# subckt_adc_TLC2574.net
KiCad netlist of a schematic drawn in Altium Designer
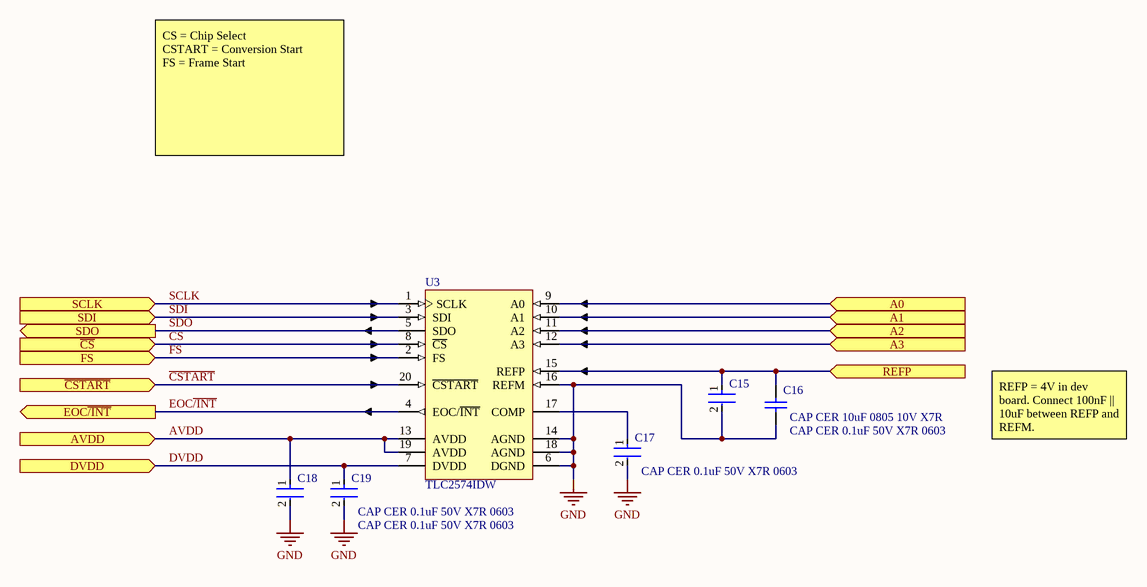
[diagram p0: subckt_adc_TLC2574.SchDoc]

(export (version "E")
  (design (tool "Eeschema 10.0.6"))
  (components
    (comp (ref "C15")
      (value "CAP CER 0.1uF 50V X7R 0603")
      (footprint "FP-CC0603-DA-MFG")
      (fields
        (field (name "OCTOPART") "https://octopart.com/cc0603krx7r7bb104-yageo-192941")
        (field (name "TOLERANCE") "0.1")
        (field (name "VOLTAGE") "16 V")
      )
      (libsource (lib "Altium Content Vault") (part "11868f565c42a9108669ba33697ecf6"))
    )
    (comp (ref "C16")
      (value "CAP CER 10uF 0805 10V X7R")
      (footprint "CAPC2013X140X50NL20T25")
      (fields
        (field (name "PART NUMBER") "0805ZC475KAT2A")
        (field (name "MANUFACTURER") "AVX Interconnect / Elco")
      )
      (libsource (lib "Altium Content Vault") (part "CAP"))
    )
    (comp (ref "C17")
      (value "CAP CER 0.1uF 50V X7R 0603")
      (footprint "FP-CC0603-DA-MFG")
      (fields
        (field (name "OCTOPART") "https://octopart.com/cc0603krx7r7bb104-yageo-192941")
        (field (name "TOLERANCE") "0.1")
        (field (name "VOLTAGE") "16 V")
      )
      (libsource (lib "Altium Content Vault") (part "11868f565c42a9108669ba33697ecf6"))
    )
    (comp (ref "C18")
      (value "CAP CER 0.1uF 50V X7R 0603")
      (footprint "FP-CC0603-DA-MFG")
      (fields
        (field (name "OCTOPART") "https://octopart.com/cc0603krx7r7bb104-yageo-192941")
        (field (name "TOLERANCE") "0.1")
        (field (name "VOLTAGE") "16 V")
      )
      (libsource (lib "Altium Content Vault") (part "11868f565c42a9108669ba33697ecf6"))
    )
    (comp (ref "C19")
      (value "CAP CER 0.1uF 50V X7R 0603")
      (footprint "FP-CC0603-DA-MFG")
      (fields
        (field (name "OCTOPART") "https://octopart.com/cc0603krx7r7bb104-yageo-192941")
        (field (name "TOLERANCE") "0.1")
        (field (name "VOLTAGE") "16 V")
      )
      (libsource (lib "Altium Content Vault") (part "11868f565c42a9108669ba33697ecf6"))
    )
    (comp (ref "U3")
      (value "TLC2574IDW")
      (footprint "TI-DW20_L")
      (fields (field (name "MANUFACTURER") "Texas Instruments"))
      (libsource (lib "Altium Content Vault") (part "TI-TLC2574DW20"))
    )
  )
  (nets
    (net (code "1") (name "/A0") (class "Default")
      (node (ref "U3") (pin "9") (pinfunction "A0_9") (pintype "input"))
    )
    (net (code "2") (name "/A1") (class "Default")
      (node (ref "U3") (pin "10") (pinfunction "A1_10") (pintype "input"))
    )
    (net (code "3") (name "/A2") (class "Default")
      (node (ref "U3") (pin "11") (pinfunction "A2_11") (pintype "input"))
    )
    (net (code "4") (name "/A3") (class "Default")
      (node (ref "U3") (pin "12") (pinfunction "A3_12") (pintype "input"))
    )
    (net (code "5") (name "/AVDD") (class "Default")
      (node (ref "C18") (pin "1") (pinfunction "1_1") (pintype "passive"))
      (node (ref "U3") (pin "13") (pinfunction "AVDD_13") (pintype "power_in"))
      (node (ref "U3") (pin "19") (pinfunction "AVDD_19") (pintype "power_in"))
    )
    (net (code "6") (name "/DVDD") (class "Default")
      (node (ref "C19") (pin "1") (pinfunction "1_1") (pintype "passive"))
      (node (ref "U3") (pin "7") (pinfunction "DVDD_7") (pintype "power_in"))
    )
    (net (code "7") (name "/EOC~{{slash}INT}") (class "Default")
      (node (ref "U3") (pin "4") (pinfunction "EOC/~{INT}_4") (pintype "output"))
    )
    (net (code "8") (name "/FS") (class "Default")
      (node (ref "U3") (pin "2") (pinfunction "FS_2") (pintype "input"))
    )
    (net (code "9") (name "/REFP") (class "Default")
      (node (ref "C15") (pin "1") (pinfunction "1_1") (pintype "passive"))
      (node (ref "C16") (pin "1") (pinfunction "1_1") (pintype "passive"))
      (node (ref "U3") (pin "15") (pinfunction "REFP_15") (pintype "input"))
    )
    (net (code "10") (name "/SCLK") (class "Default")
      (node (ref "U3") (pin "1") (pinfunction "SCLK_1") (pintype "input"))
    )
    (net (code "11") (name "/SDI") (class "Default")
      (node (ref "U3") (pin "3") (pinfunction "SDI_3") (pintype "input"))
    )
    (net (code "12") (name "/SDO") (class "Default")
      (node (ref "U3") (pin "5") (pinfunction "SDO_5") (pintype "tri_state"))
    )
    (net (code "13") (name "/~{CSTART}") (class "Default")
      (node (ref "U3") (pin "20") (pinfunction "~{CSTART}_20") (pintype "input"))
    )
    (net (code "14") (name "/~{CS}") (class "Default")
      (node (ref "U3") (pin "8") (pinfunction "~{CS}_8") (pintype "input"))
    )
    (net (code "15") (name "GND") (class "Default")
      (node (ref "C15") (pin "2") (pinfunction "2_2") (pintype "passive"))
      (node (ref "C16") (pin "2") (pinfunction "2_2") (pintype "passive"))
      (node (ref "C17") (pin "2") (pinfunction "2_2") (pintype "passive"))
      (node (ref "C18") (pin "2") (pinfunction "2_2") (pintype "passive"))
      (node (ref "C19") (pin "2") (pinfunction "2_2") (pintype "passive"))
      (node (ref "U3") (pin "14") (pinfunction "AGND_14") (pintype "power_in"))
      (node (ref "U3") (pin "16") (pinfunction "REFM_16") (pintype "input"))
      (node (ref "U3") (pin "18") (pinfunction "AGND_18") (pintype "power_in"))
      (node (ref "U3") (pin "6") (pinfunction "DGND_6") (pintype "power_in"))
    )
    (net (code "16") (name "Net-(U3-COMP)") (class "Default")
      (node (ref "C17") (pin "1") (pinfunction "1_1") (pintype "passive"))
      (node (ref "U3") (pin "17") (pinfunction "COMP_17") (pintype "passive"))
    )
  )
)
